# Video.net
KiCad netlist of a schematic drawn in Altium Designer
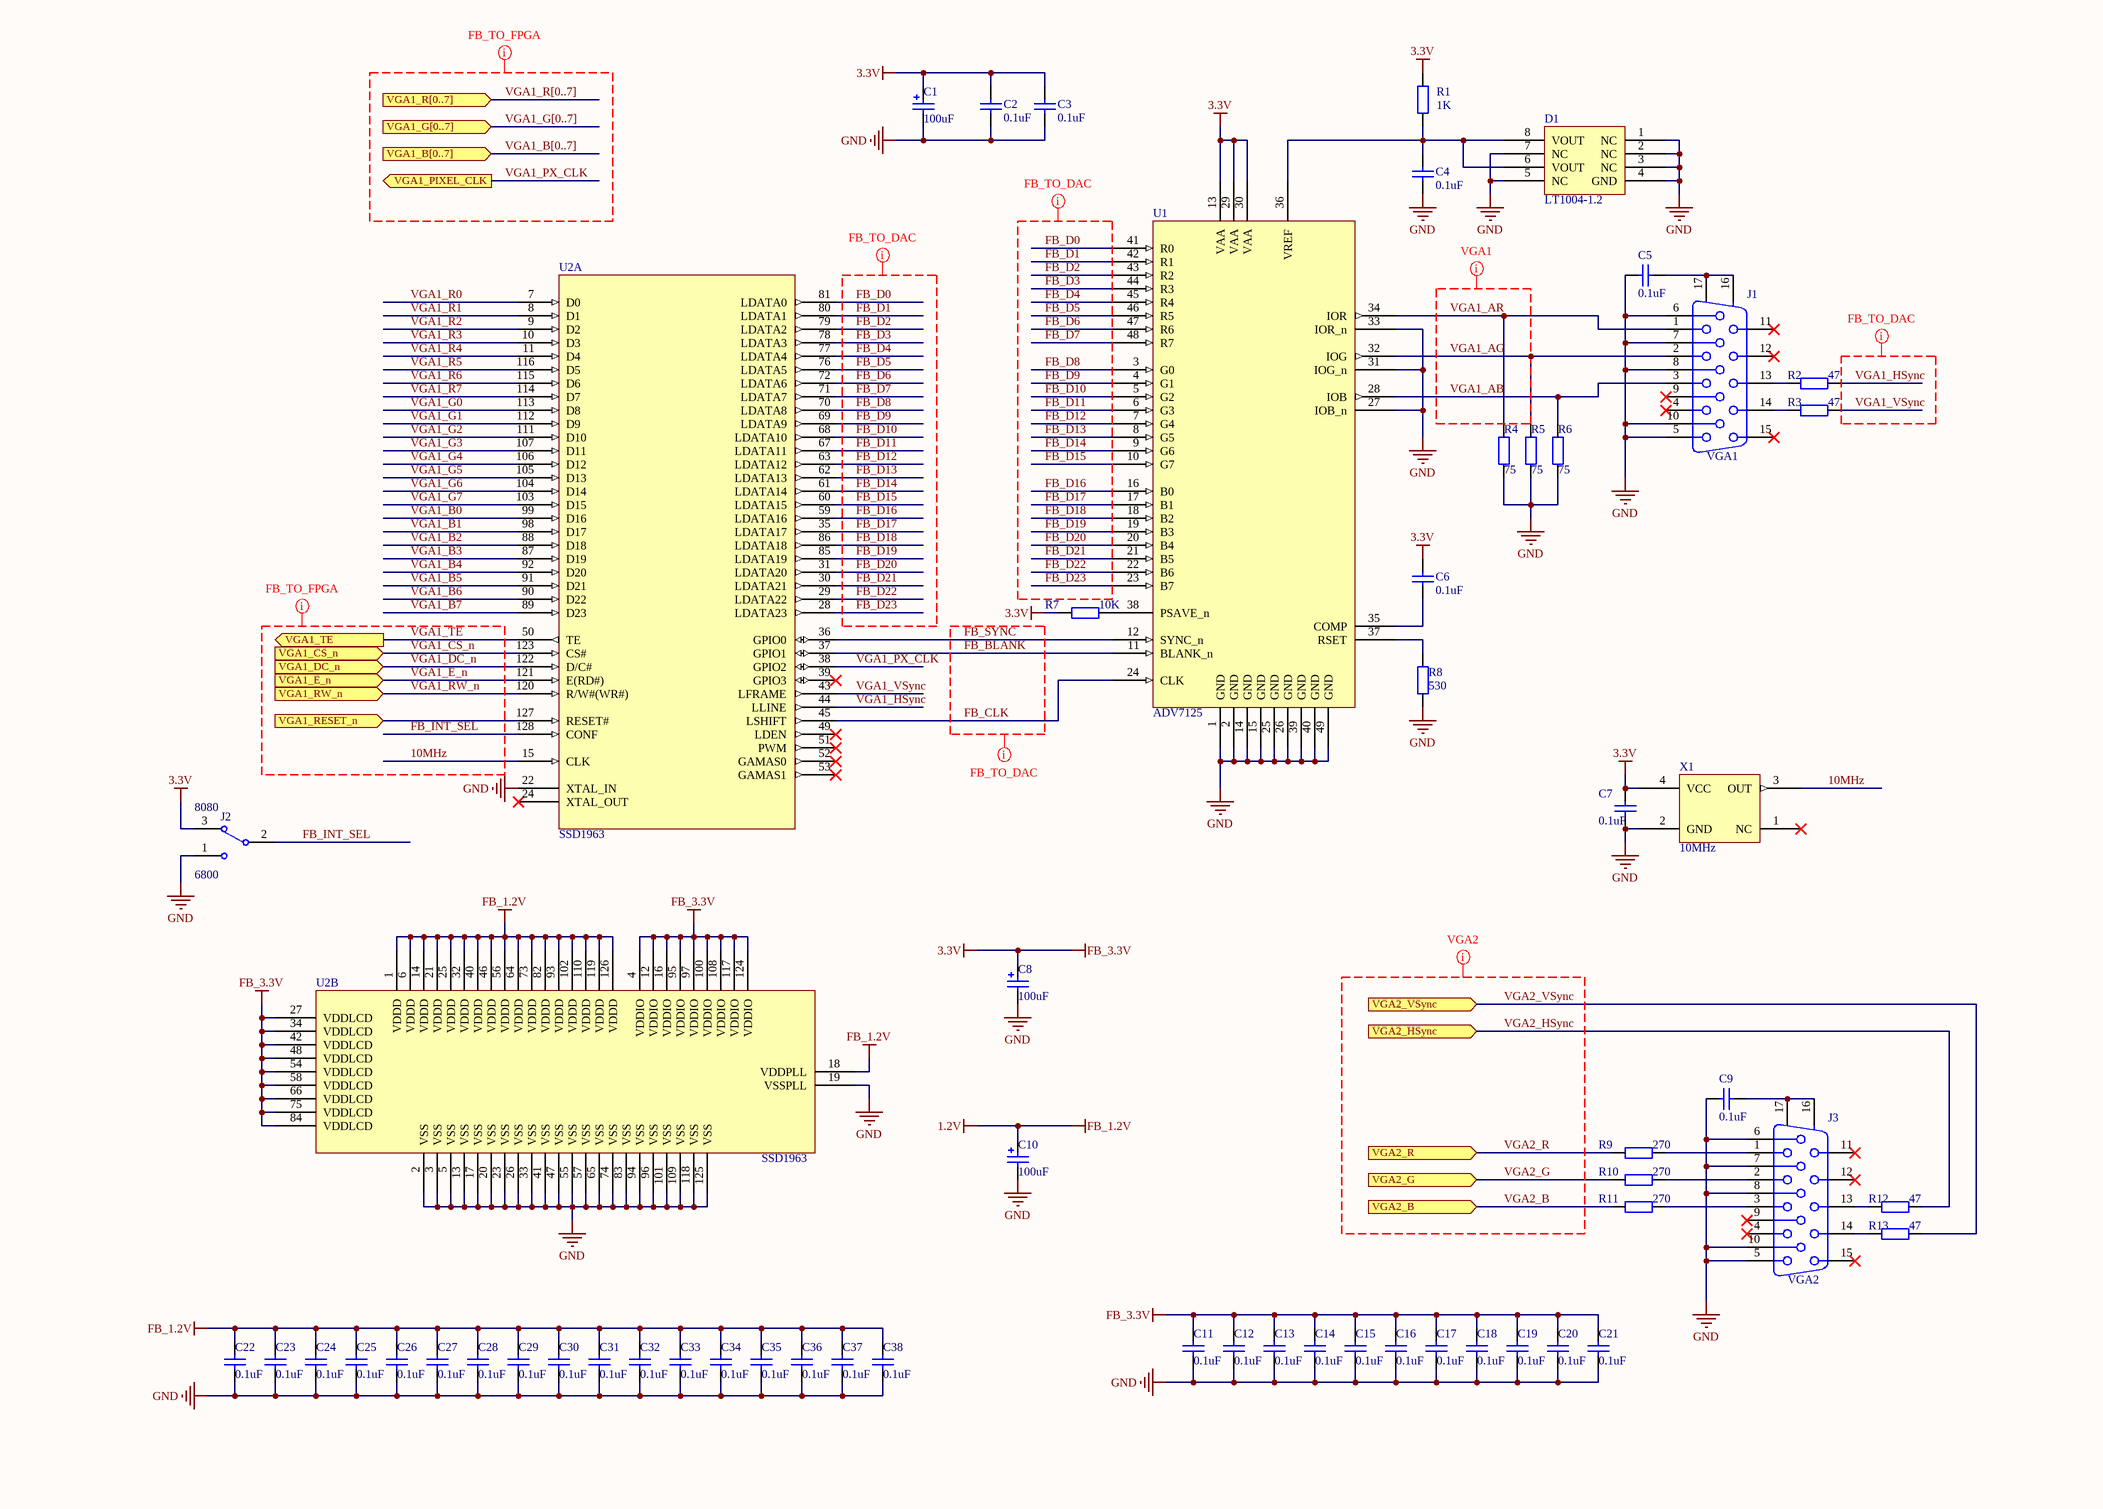
[diagram p0: Video.SchDoc]

(export (version "E")
  (design (tool "Eeschema 10.0.6"))
  (components
    (comp (ref "C1")
      (value "100uF")
      (footprint "C1206_POLARIZED")
      (description "Polarized Capacitor (Axial)")
      (fields (field (name "Comment") "Cap Pol2") (field (name "PUBLISHER") "Altium Limited"))
      (libsource (lib "Miscellaneous Devices") (part "Cap Pol2"))
    )
    (comp (ref "C2")
      (value "0.1uF")
      (footprint "0402")
      (description "Capacitor")
      (fields (field (name "Comment") "Cap") (field (name "PUBLISHER") "Altium Limited"))
      (libsource (lib "Miscellaneous Devices") (part "Cap"))
    )
    (comp (ref "C3")
      (value "0.1uF")
      (footprint "0402")
      (description "Capacitor")
      (fields (field (name "Comment") "Cap") (field (name "PUBLISHER") "Altium Limited"))
      (libsource (lib "Miscellaneous Devices") (part "Cap"))
    )
    (comp (ref "C4")
      (value "0.1uF")
      (footprint "0402")
      (description "Capacitor")
      (fields (field (name "Comment") "Cap") (field (name "PUBLISHER") "Altium Limited"))
      (libsource (lib "Miscellaneous Devices") (part "Cap"))
    )
    (comp (ref "C5")
      (value "0.1uF")
      (footprint "0402")
      (description "Capacitor")
      (fields (field (name "Comment") "Cap") (field (name "PUBLISHER") "Altium Limited"))
      (libsource (lib "Miscellaneous Devices") (part "Cap"))
    )
    (comp (ref "C6")
      (value "0.1uF")
      (footprint "0402")
      (description "Capacitor")
      (fields (field (name "Comment") "Cap") (field (name "PUBLISHER") "Altium Limited"))
      (libsource (lib "Miscellaneous Devices") (part "Cap"))
    )
    (comp (ref "C7")
      (value "0.1uF")
      (footprint "0402")
      (description "Capacitor")
      (fields (field (name "Comment") "Cap") (field (name "PUBLISHER") "Altium Limited"))
      (libsource (lib "Miscellaneous Devices") (part "Cap"))
    )
    (comp (ref "C8")
      (value "100uF")
      (footprint "C1206_POLARIZED")
      (description "Polarized Capacitor (Axial)")
      (fields (field (name "Comment") "Cap Pol2") (field (name "PUBLISHER") "Altium Limited"))
      (libsource (lib "Miscellaneous Devices") (part "Cap Pol2"))
    )
    (comp (ref "C9")
      (value "0.1uF")
      (footprint "0402")
      (description "Capacitor")
      (fields (field (name "Comment") "Cap") (field (name "PUBLISHER") "Altium Limited"))
      (libsource (lib "Miscellaneous Devices") (part "Cap"))
    )
    (comp (ref "C10")
      (value "100uF")
      (footprint "C1206_POLARIZED")
      (description "Polarized Capacitor (Axial)")
      (fields (field (name "Comment") "Cap Pol2") (field (name "PUBLISHER") "Altium Limited"))
      (libsource (lib "Miscellaneous Devices") (part "Cap Pol2"))
    )
    (comp (ref "C11")
      (value "0.1uF")
      (footprint "0402")
      (description "Capacitor")
      (fields (field (name "Comment") "Cap") (field (name "PUBLISHER") "Altium Limited"))
      (libsource (lib "Miscellaneous Devices") (part "Cap"))
    )
    (comp (ref "C12")
      (value "0.1uF")
      (footprint "0402")
      (description "Capacitor")
      (fields (field (name "Comment") "Cap") (field (name "PUBLISHER") "Altium Limited"))
      (libsource (lib "Miscellaneous Devices") (part "Cap"))
    )
    (comp (ref "C13")
      (value "0.1uF")
      (footprint "0402")
      (description "Capacitor")
      (fields (field (name "Comment") "Cap") (field (name "PUBLISHER") "Altium Limited"))
      (libsource (lib "Miscellaneous Devices") (part "Cap"))
    )
    (comp (ref "C14")
      (value "0.1uF")
      (footprint "0402")
      (description "Capacitor")
      (fields (field (name "Comment") "Cap") (field (name "PUBLISHER") "Altium Limited"))
      (libsource (lib "Miscellaneous Devices") (part "Cap"))
    )
    (comp (ref "C15")
      (value "0.1uF")
      (footprint "0402")
      (description "Capacitor")
      (fields (field (name "Comment") "Cap") (field (name "PUBLISHER") "Altium Limited"))
      (libsource (lib "Miscellaneous Devices") (part "Cap"))
    )
    (comp (ref "C16")
      (value "0.1uF")
      (footprint "0402")
      (description "Capacitor")
      (fields (field (name "Comment") "Cap") (field (name "PUBLISHER") "Altium Limited"))
      (libsource (lib "Miscellaneous Devices") (part "Cap"))
    )
    (comp (ref "C17")
      (value "0.1uF")
      (footprint "0402")
      (description "Capacitor")
      (fields (field (name "Comment") "Cap") (field (name "PUBLISHER") "Altium Limited"))
      (libsource (lib "Miscellaneous Devices") (part "Cap"))
    )
    (comp (ref "C18")
      (value "0.1uF")
      (footprint "0402")
      (description "Capacitor")
      (fields (field (name "Comment") "Cap") (field (name "PUBLISHER") "Altium Limited"))
      (libsource (lib "Miscellaneous Devices") (part "Cap"))
    )
    (comp (ref "C19")
      (value "0.1uF")
      (footprint "0402")
      (description "Capacitor")
      (fields (field (name "Comment") "Cap") (field (name "PUBLISHER") "Altium Limited"))
      (libsource (lib "Miscellaneous Devices") (part "Cap"))
    )
    (comp (ref "C20")
      (value "0.1uF")
      (footprint "0402")
      (description "Capacitor")
      (fields (field (name "Comment") "Cap") (field (name "PUBLISHER") "Altium Limited"))
      (libsource (lib "Miscellaneous Devices") (part "Cap"))
    )
    (comp (ref "C21")
      (value "0.1uF")
      (footprint "0402")
      (description "Capacitor")
      (fields (field (name "Comment") "Cap") (field (name "PUBLISHER") "Altium Limited"))
      (libsource (lib "Miscellaneous Devices") (part "Cap"))
    )
    (comp (ref "C22")
      (value "0.1uF")
      (footprint "0402")
      (description "Capacitor")
      (fields (field (name "Comment") "Cap") (field (name "PUBLISHER") "Altium Limited"))
      (libsource (lib "Miscellaneous Devices") (part "Cap"))
    )
    (comp (ref "C23")
      (value "0.1uF")
      (footprint "0402")
      (description "Capacitor")
      (fields (field (name "Comment") "Cap") (field (name "PUBLISHER") "Altium Limited"))
      (libsource (lib "Miscellaneous Devices") (part "Cap"))
    )
    (comp (ref "C24")
      (value "0.1uF")
      (footprint "0402")
      (description "Capacitor")
      (fields (field (name "Comment") "Cap") (field (name "PUBLISHER") "Altium Limited"))
      (libsource (lib "Miscellaneous Devices") (part "Cap"))
    )
    (comp (ref "C25")
      (value "0.1uF")
      (footprint "0402")
      (description "Capacitor")
      (fields (field (name "Comment") "Cap") (field (name "PUBLISHER") "Altium Limited"))
      (libsource (lib "Miscellaneous Devices") (part "Cap"))
    )
    (comp (ref "C26")
      (value "0.1uF")
      (footprint "0402")
      (description "Capacitor")
      (fields (field (name "Comment") "Cap") (field (name "PUBLISHER") "Altium Limited"))
      (libsource (lib "Miscellaneous Devices") (part "Cap"))
    )
    (comp (ref "C27")
      (value "0.1uF")
      (footprint "0402")
      (description "Capacitor")
      (fields (field (name "Comment") "Cap") (field (name "PUBLISHER") "Altium Limited"))
      (libsource (lib "Miscellaneous Devices") (part "Cap"))
    )
    (comp (ref "C28")
      (value "0.1uF")
      (footprint "0402")
      (description "Capacitor")
      (fields (field (name "Comment") "Cap") (field (name "PUBLISHER") "Altium Limited"))
      (libsource (lib "Miscellaneous Devices") (part "Cap"))
    )
    (comp (ref "C29")
      (value "0.1uF")
      (footprint "0402")
      (description "Capacitor")
      (fields (field (name "Comment") "Cap") (field (name "PUBLISHER") "Altium Limited"))
      (libsource (lib "Miscellaneous Devices") (part "Cap"))
    )
    (comp (ref "C30")
      (value "0.1uF")
      (footprint "0402")
      (description "Capacitor")
      (fields (field (name "Comment") "Cap") (field (name "PUBLISHER") "Altium Limited"))
      (libsource (lib "Miscellaneous Devices") (part "Cap"))
    )
    (comp (ref "C31")
      (value "0.1uF")
      (footprint "0402")
      (description "Capacitor")
      (fields (field (name "Comment") "Cap") (field (name "PUBLISHER") "Altium Limited"))
      (libsource (lib "Miscellaneous Devices") (part "Cap"))
    )
    (comp (ref "C32")
      (value "0.1uF")
      (footprint "0402")
      (description "Capacitor")
      (fields (field (name "Comment") "Cap") (field (name "PUBLISHER") "Altium Limited"))
      (libsource (lib "Miscellaneous Devices") (part "Cap"))
    )
    (comp (ref "C33")
      (value "0.1uF")
      (footprint "0402")
      (description "Capacitor")
      (fields (field (name "Comment") "Cap") (field (name "PUBLISHER") "Altium Limited"))
      (libsource (lib "Miscellaneous Devices") (part "Cap"))
    )
    (comp (ref "C34")
      (value "0.1uF")
      (footprint "0402")
      (description "Capacitor")
      (fields (field (name "Comment") "Cap") (field (name "PUBLISHER") "Altium Limited"))
      (libsource (lib "Miscellaneous Devices") (part "Cap"))
    )
    (comp (ref "C35")
      (value "0.1uF")
      (footprint "0402")
      (description "Capacitor")
      (fields (field (name "Comment") "Cap") (field (name "PUBLISHER") "Altium Limited"))
      (libsource (lib "Miscellaneous Devices") (part "Cap"))
    )
    (comp (ref "C36")
      (value "0.1uF")
      (footprint "0402")
      (description "Capacitor")
      (fields (field (name "Comment") "Cap") (field (name "PUBLISHER") "Altium Limited"))
      (libsource (lib "Miscellaneous Devices") (part "Cap"))
    )
    (comp (ref "C37")
      (value "0.1uF")
      (footprint "0402")
      (description "Capacitor")
      (fields (field (name "Comment") "Cap") (field (name "PUBLISHER") "Altium Limited"))
      (libsource (lib "Miscellaneous Devices") (part "Cap"))
    )
    (comp (ref "C38")
      (value "0.1uF")
      (footprint "0402")
      (description "Capacitor")
      (fields (field (name "Comment") "Cap") (field (name "PUBLISHER") "Altium Limited"))
      (libsource (lib "Miscellaneous Devices") (part "Cap"))
    )
    (comp (ref "D1") (value "LT1004-1.2") (footprint "S8") (libsource (lib "FPGA_board") (part "LT1004-1.2")))
    (comp (ref "J1")
      (value "VGA1")
      (footprint "FPGA_board:VGA_Socket")
      (description "Receptacle Assembly, 15-Pin, Sim Line Connector")
      (libsource (lib "Miscellaneous Connectors") (part "Connector 15"))
    )
    (comp (ref "J2")
      (value "FB_INTERFACE")
      (footprint "HDR1X3")
      (fields (field (name "PUBLISHER") "Altium Limited"))
      (libsource (lib "Miscellaneous Devices") (part "SW-SPDT"))
    )
    (comp (ref "J3")
      (value "VGA2")
      (footprint "FPGA_board:VGA_Socket")
      (description "Receptacle Assembly, 15-Pin, Sim Line Connector")
      (libsource (lib "Miscellaneous Connectors") (part "Connector 15"))
    )
    (comp (ref "R1")
      (value "1K")
      (footprint "J1-0603")
      (description "Resistor")
      (fields (field (name "Comment") "Res2") (field (name "PUBLISHER") "Altium Limited"))
      (libsource (lib "") (part "Res2_2"))
    )
    (comp (ref "R2")
      (value "47")
      (footprint "J1-0603")
      (description "Resistor")
      (fields (field (name "Comment") "Res2") (field (name "PUBLISHER") "Altium Limited"))
      (libsource (lib "") (part "Res2_1"))
    )
    (comp (ref "R3")
      (value "47")
      (footprint "J1-0603")
      (description "Resistor")
      (fields (field (name "Comment") "Res2") (field (name "PUBLISHER") "Altium Limited"))
      (libsource (lib "") (part "Res2_1"))
    )
    (comp (ref "R4")
      (value "75")
      (footprint "J1-0603")
      (description "Resistor")
      (fields (field (name "Comment") "Res2") (field (name "PUBLISHER") "Altium Limited"))
      (libsource (lib "") (part "Res2_2"))
    )
    (comp (ref "R5")
      (value "75")
      (footprint "J1-0603")
      (description "Resistor")
      (fields (field (name "Comment") "Res2") (field (name "PUBLISHER") "Altium Limited"))
      (libsource (lib "") (part "Res2_3"))
    )
    (comp (ref "R6")
      (value "75")
      (footprint "J1-0603")
      (description "Resistor")
      (fields (field (name "Comment") "Res2") (field (name "PUBLISHER") "Altium Limited"))
      (libsource (lib "") (part "Res2_3"))
    )
    (comp (ref "R7")
      (value "10K")
      (footprint "J1-0603")
      (description "Resistor")
      (fields (field (name "Comment") "Res2") (field (name "PUBLISHER") "Altium Limited"))
      (libsource (lib "") (part "Res2_1"))
    )
    (comp (ref "R8")
      (value "530")
      (footprint "J1-0603")
      (description "Resistor")
      (fields (field (name "Comment") "Res2") (field (name "PUBLISHER") "Altium Limited"))
      (libsource (lib "") (part "Res2_2"))
    )
    (comp (ref "R9")
      (value "270")
      (footprint "6-0805_N")
      (description "Resistor")
      (fields (field (name "Comment") "Res2") (field (name "PUBLISHER") "Altium Limited"))
      (libsource (lib "Miscellaneous Devices") (part "Res2"))
    )
    (comp (ref "R10")
      (value "270")
      (footprint "6-0805_N")
      (description "Resistor")
      (fields (field (name "Comment") "Res2") (field (name "PUBLISHER") "Altium Limited"))
      (libsource (lib "Miscellaneous Devices") (part "Res2"))
    )
    (comp (ref "R11")
      (value "270")
      (footprint "6-0805_N")
      (description "Resistor")
      (fields (field (name "Comment") "Res2") (field (name "PUBLISHER") "Altium Limited"))
      (libsource (lib "Miscellaneous Devices") (part "Res2"))
    )
    (comp (ref "R12")
      (value "47")
      (footprint "J1-0603")
      (description "Resistor")
      (fields (field (name "Comment") "Res2") (field (name "PUBLISHER") "Altium Limited"))
      (libsource (lib "") (part "Res2_1"))
    )
    (comp (ref "R13")
      (value "47")
      (footprint "J1-0603")
      (description "Resistor")
      (fields (field (name "Comment") "Res2") (field (name "PUBLISHER") "Altium Limited"))
      (libsource (lib "") (part "Res2_1"))
    )
    (comp (ref "U1")
      (value "ADV7125")
      (footprint "LFCSP_VQ48")
      (libsource (lib "FPGA_board") (part "ADV7125"))
    )
    (comp (ref "U2")
      (value "SSD1963")
      (footprint "LQFP128-0.4")
      (libsource (lib "FPGA_board") (part "SSD1963"))
    )
    (comp (ref "X1")
      (value "10MHz")
      (footprint "FOX924")
      (libsource (lib "FPGA_board") (part "FOX924B-10MHz"))
    )
  )
  (nets
    (net (code "1") (name "/10MHz") (class "Default")
      (node (ref "U2") (pin "15") (pinfunction "CLK_15") (pintype "input"))
      (node (ref "X1") (pin "3") (pinfunction "OUT_3") (pintype "output"))
    )
    (net (code "2") (name "/FB_BLANK") (class "Default")
      (node (ref "U1") (pin "11") (pinfunction "BLANK_n_11") (pintype "input"))
      (node (ref "U2") (pin "37") (pinfunction "GPIO1_37") (pintype "bidirectional"))
    )
    (net (code "3") (name "/FB_CLK") (class "Default")
      (node (ref "U1") (pin "24") (pinfunction "CLK_24") (pintype "input"))
      (node (ref "U2") (pin "45") (pinfunction "LSHIFT_45") (pintype "output"))
    )
    (net (code "4") (name "/FB_D0") (class "Default")
      (node (ref "U1") (pin "41") (pinfunction "R0_41") (pintype "input"))
      (node (ref "U2") (pin "81") (pinfunction "LDATA0_81") (pintype "output"))
    )
    (net (code "5") (name "/FB_D1") (class "Default")
      (node (ref "U1") (pin "42") (pinfunction "R1_42") (pintype "input"))
      (node (ref "U2") (pin "80") (pinfunction "LDATA1_80") (pintype "output"))
    )
    (net (code "6") (name "/FB_D2") (class "Default")
      (node (ref "U1") (pin "43") (pinfunction "R2_43") (pintype "input"))
      (node (ref "U2") (pin "79") (pinfunction "LDATA2_79") (pintype "output"))
    )
    (net (code "7") (name "/FB_D3") (class "Default")
      (node (ref "U1") (pin "44") (pinfunction "R3_44") (pintype "input"))
      (node (ref "U2") (pin "78") (pinfunction "LDATA3_78") (pintype "output"))
    )
    (net (code "8") (name "/FB_D4") (class "Default")
      (node (ref "U1") (pin "45") (pinfunction "R4_45") (pintype "input"))
      (node (ref "U2") (pin "77") (pinfunction "LDATA4_77") (pintype "output"))
    )
    (net (code "9") (name "/FB_D5") (class "Default")
      (node (ref "U1") (pin "46") (pinfunction "R5_46") (pintype "input"))
      (node (ref "U2") (pin "76") (pinfunction "LDATA5_76") (pintype "output"))
    )
    (net (code "10") (name "/FB_D6") (class "Default")
      (node (ref "U1") (pin "47") (pinfunction "R6_47") (pintype "input"))
      (node (ref "U2") (pin "72") (pinfunction "LDATA6_72") (pintype "output"))
    )
    (net (code "11") (name "/FB_D7") (class "Default")
      (node (ref "U1") (pin "48") (pinfunction "R7_48") (pintype "input"))
      (node (ref "U2") (pin "71") (pinfunction "LDATA7_71") (pintype "output"))
    )
    (net (code "12") (name "/FB_D8") (class "Default")
      (node (ref "U1") (pin "3") (pinfunction "G0_3") (pintype "input"))
      (node (ref "U2") (pin "70") (pinfunction "LDATA8_70") (pintype "output"))
    )
    (net (code "13") (name "/FB_D9") (class "Default")
      (node (ref "U1") (pin "4") (pinfunction "G1_4") (pintype "input"))
      (node (ref "U2") (pin "69") (pinfunction "LDATA9_69") (pintype "output"))
    )
    (net (code "14") (name "/FB_D10") (class "Default")
      (node (ref "U1") (pin "5") (pinfunction "G2_5") (pintype "input"))
      (node (ref "U2") (pin "68") (pinfunction "LDATA10_68") (pintype "output"))
    )
    (net (code "15") (name "/FB_D11") (class "Default")
      (node (ref "U1") (pin "6") (pinfunction "G3_6") (pintype "input"))
      (node (ref "U2") (pin "67") (pinfunction "LDATA11_67") (pintype "output"))
    )
    (net (code "16") (name "/FB_D12") (class "Default")
      (node (ref "U1") (pin "7") (pinfunction "G4_7") (pintype "input"))
      (node (ref "U2") (pin "63") (pinfunction "LDATA12_63") (pintype "output"))
    )
    (net (code "17") (name "/FB_D13") (class "Default")
      (node (ref "U1") (pin "8") (pinfunction "G5_8") (pintype "input"))
      (node (ref "U2") (pin "62") (pinfunction "LDATA13_62") (pintype "output"))
    )
    (net (code "18") (name "/FB_D14") (class "Default")
      (node (ref "U1") (pin "9") (pinfunction "G6_9") (pintype "input"))
      (node (ref "U2") (pin "61") (pinfunction "LDATA14_61") (pintype "output"))
    )
    (net (code "19") (name "/FB_D15") (class "Default")
      (node (ref "U1") (pin "10") (pinfunction "G7_10") (pintype "input"))
      (node (ref "U2") (pin "60") (pinfunction "LDATA15_60") (pintype "output"))
    )
    (net (code "20") (name "/FB_D16") (class "Default")
      (node (ref "U1") (pin "16") (pinfunction "B0_16") (pintype "input"))
      (node (ref "U2") (pin "59") (pinfunction "LDATA16_59") (pintype "output"))
    )
    (net (code "21") (name "/FB_D17") (class "Default")
      (node (ref "U1") (pin "17") (pinfunction "B1_17") (pintype "input"))
      (node (ref "U2") (pin "35") (pinfunction "LDATA17_35") (pintype "output"))
    )
    (net (code "22") (name "/FB_D18") (class "Default")
      (node (ref "U1") (pin "18") (pinfunction "B2_18") (pintype "input"))
      (node (ref "U2") (pin "86") (pinfunction "LDATA18_86") (pintype "output"))
    )
    (net (code "23") (name "/FB_D19") (class "Default")
      (node (ref "U1") (pin "19") (pinfunction "B3_19") (pintype "input"))
      (node (ref "U2") (pin "85") (pinfunction "LDATA19_85") (pintype "output"))
    )
    (net (code "24") (name "/FB_D20") (class "Default")
      (node (ref "U1") (pin "20") (pinfunction "B4_20") (pintype "input"))
      (node (ref "U2") (pin "31") (pinfunction "LDATA20_31") (pintype "output"))
    )
    (net (code "25") (name "/FB_D21") (class "Default")
      (node (ref "U1") (pin "21") (pinfunction "B5_21") (pintype "input"))
      (node (ref "U2") (pin "30") (pinfunction "LDATA21_30") (pintype "output"))
    )
    (net (code "26") (name "/FB_D22") (class "Default")
      (node (ref "U1") (pin "22") (pinfunction "B6_22") (pintype "input"))
      (node (ref "U2") (pin "29") (pinfunction "LDATA22_29") (pintype "output"))
    )
    (net (code "27") (name "/FB_D23") (class "Default")
      (node (ref "U1") (pin "23") (pinfunction "B7_23") (pintype "input"))
      (node (ref "U2") (pin "28") (pinfunction "LDATA23_28") (pintype "output"))
    )
    (net (code "28") (name "/FB_INT_SEL") (class "Default")
      (node (ref "J2") (pin "2") (pinfunction "2_2") (pintype "passive"))
      (node (ref "U2") (pin "128") (pinfunction "CONF_128") (pintype "input"))
    )
    (net (code "29") (name "/FB_SYNC") (class "Default")
      (node (ref "U1") (pin "12") (pinfunction "SYNC_n_12") (pintype "input"))
      (node (ref "U2") (pin "36") (pinfunction "GPIO0_36") (pintype "bidirectional"))
    )
    (net (code "30") (name "/VGA1_AB") (class "Default")
      (node (ref "J1") (pin "3") (pinfunction "3_3") (pintype "passive"))
      (node (ref "R6") (pin "1") (pinfunction "1_1") (pintype "passive"))
      (node (ref "U1") (pin "28") (pinfunction "IOB_28") (pintype "output"))
    )
    (net (code "31") (name "/VGA1_AG") (class "Default")
      (node (ref "J1") (pin "2") (pinfunction "2_2") (pintype "passive"))
      (node (ref "R5") (pin "1") (pinfunction "1_1") (pintype "passive"))
      (node (ref "U1") (pin "32") (pinfunction "IOG_32") (pintype "output"))
    )
    (net (code "32") (name "/VGA1_AR") (class "Default")
      (node (ref "J1") (pin "1") (pinfunction "1_1") (pintype "passive"))
      (node (ref "R4") (pin "2") (pinfunction "2_2") (pintype "passive"))
      (node (ref "U1") (pin "34") (pinfunction "IOR_34") (pintype "output"))
    )
    (net (code "33") (name "/VGA1_B0") (class "Default")
      (node (ref "U2") (pin "99") (pinfunction "D16_99") (pintype "input"))
    )
    (net (code "34") (name "/VGA1_B1") (class "Default")
      (node (ref "U2") (pin "98") (pinfunction "D17_98") (pintype "input"))
    )
    (net (code "35") (name "/VGA1_B2") (class "Default")
      (node (ref "U2") (pin "88") (pinfunction "D18_88") (pintype "input"))
    )
    (net (code "36") (name "/VGA1_B3") (class "Default")
      (node (ref "U2") (pin "87") (pinfunction "D19_87") (pintype "input"))
    )
    (net (code "37") (name "/VGA1_B4") (class "Default")
      (node (ref "U2") (pin "92") (pinfunction "D20_92") (pintype "input"))
    )
    (net (code "38") (name "/VGA1_B5") (class "Default")
      (node (ref "U2") (pin "91") (pinfunction "D21_91") (pintype "input"))
    )
    (net (code "39") (name "/VGA1_B6") (class "Default")
      (node (ref "U2") (pin "90") (pinfunction "D22_90") (pintype "input"))
    )
    (net (code "40") (name "/VGA1_B7") (class "Default")
      (node (ref "U2") (pin "89") (pinfunction "D23_89") (pintype "input"))
    )
    (net (code "42") (name "/VGA1_CS_n") (class "Default")
      (node (ref "U2") (pin "123") (pinfunction "CS#_123") (pintype "input"))
    )
    (net (code "43") (name "/VGA1_DC_n") (class "Default")
      (node (ref "U2") (pin "122") (pinfunction "D/C#_122") (pintype "input"))
    )
    (net (code "44") (name "/VGA1_E_n") (class "Default")
      (node (ref "U2") (pin "121") (pinfunction "E(RD#)_121") (pintype "input"))
    )
    (net (code "45") (name "/VGA1_G0") (class "Default")
      (node (ref "U2") (pin "113") (pinfunction "D8_113") (pintype "input"))
    )
    (net (code "46") (name "/VGA1_G1") (class "Default")
      (node (ref "U2") (pin "112") (pinfunction "D9_112") (pintype "input"))
    )
    (net (code "47") (name "/VGA1_G2") (class "Default")
      (node (ref "U2") (pin "111") (pinfunction "D10_111") (pintype "input"))
    )
    (net (code "48") (name "/VGA1_G3") (class "Default")
      (node (ref "U2") (pin "107") (pinfunction "D11_107") (pintype "input"))
    )
    (net (code "49") (name "/VGA1_G4") (class "Default")
      (node (ref "U2") (pin "106") (pinfunction "D12_106") (pintype "input"))
    )
    (net (code "50") (name "/VGA1_G5") (class "Default")
      (node (ref "U2") (pin "105") (pinfunction "D13_105") (pintype "input"))
    )
    (net (code "51") (name "/VGA1_G6") (class "Default")
      (node (ref "U2") (pin "104") (pinfunction "D14_104") (pintype "input"))
    )
    (net (code "52") (name "/VGA1_G7") (class "Default")
      (node (ref "U2") (pin "103") (pinfunction "D15_103") (pintype "input"))
    )
    (net (code "54") (name "/VGA1_HSync") (class "Default")
      (node (ref "R2") (pin "2") (pinfunction "2_2") (pintype "passive"))
      (node (ref "U2") (pin "44") (pinfunction "LLINE_44") (pintype "output"))
    )
    (net (code "55") (name "/VGA1_PX_CLK") (class "Default")
      (node (ref "U2") (pin "38") (pinfunction "GPIO2_38") (pintype "bidirectional"))
    )
    (net (code "56") (name "/VGA1_R0") (class "Default")
      (node (ref "U2") (pin "7") (pinfunction "D0_7") (pintype "input"))
    )
    (net (code "57") (name "/VGA1_R1") (class "Default")
      (node (ref "U2") (pin "8") (pinfunction "D1_8") (pintype "input"))
    )
    (net (code "58") (name "/VGA1_R2") (class "Default")
      (node (ref "U2") (pin "9") (pinfunction "D2_9") (pintype "input"))
    )
    (net (code "59") (name "/VGA1_R3") (class "Default")
      (node (ref "U2") (pin "10") (pinfunction "D3_10") (pintype "input"))
    )
    (net (code "60") (name "/VGA1_R4") (class "Default")
      (node (ref "U2") (pin "11") (pinfunction "D4_11") (pintype "input"))
    )
    (net (code "61") (name "/VGA1_R5") (class "Default")
      (node (ref "U2") (pin "116") (pinfunction "D5_116") (pintype "input"))
    )
    (net (code "62") (name "/VGA1_R6") (class "Default")
      (node (ref "U2") (pin "115") (pinfunction "D6_115") (pintype "input"))
    )
    (net (code "63") (name "/VGA1_R7") (class "Default")
      (node (ref "U2") (pin "114") (pinfunction "D7_114") (pintype "input"))
    )
    (net (code "64") (name "/VGA1_RESET_n") (class "Default")
      (node (ref "U2") (pin "127") (pinfunction "RESET#_127") (pintype "input"))
    )
    (net (code "65") (name "/VGA1_RW_n") (class "Default")
      (node (ref "U2") (pin "120") (pinfunction "R/W#(WR#)_120") (pintype "input"))
    )
    (net (code "67") (name "/VGA1_TE") (class "Default")
      (node (ref "U2") (pin "50") (pinfunction "TE_50") (pintype "output"))
    )
    (net (code "68") (name "/VGA1_VSync") (class "Default")
      (node (ref "R3") (pin "2") (pinfunction "2_2") (pintype "passive"))
      (node (ref "U2") (pin "43") (pinfunction "LFRAME_43") (pintype "output"))
    )
    (net (code "69") (name "/VGA2_B") (class "Default")
      (node (ref "R11") (pin "2") (pinfunction "2_2") (pintype "passive"))
    )
    (net (code "70") (name "/VGA2_G") (class "Default")
      (node (ref "R10") (pin "2") (pinfunction "2_2") (pintype "passive"))
    )
    (net (code "71") (name "/VGA2_HSync") (class "Default")
      (node (ref "R12") (pin "2") (pinfunction "2_2") (pintype "passive"))
    )
    (net (code "72") (name "/VGA2_R") (class "Default")
      (node (ref "R9") (pin "2") (pinfunction "2_2") (pintype "passive"))
    )
    (net (code "73") (name "/VGA2_VSync") (class "Default")
      (node (ref "R13") (pin "2") (pinfunction "2_2") (pintype "passive"))
    )
    (net (code "74") (name "1.2V") (class "Default")
      (node (ref "C10") (pin "1") (pinfunction "1_1") (pintype "passive"))
      (node (ref "C22") (pin "1") (pinfunction "1_1") (pintype "passive"))
      (node (ref "C23") (pin "1") (pinfunction "1_1") (pintype "passive"))
      (node (ref "C24") (pin "1") (pinfunction "1_1") (pintype "passive"))
      (node (ref "C25") (pin "1") (pinfunction "1_1") (pintype "passive"))
      (node (ref "C26") (pin "1") (pinfunction "1_1") (pintype "passive"))
      (node (ref "C27") (pin "1") (pinfunction "1_1") (pintype "passive"))
      (node (ref "C28") (pin "1") (pinfunction "1_1") (pintype "passive"))
      (node (ref "C29") (pin "1") (pinfunction "1_1") (pintype "passive"))
      (node (ref "C30") (pin "1") (pinfunction "1_1") (pintype "passive"))
      (node (ref "C31") (pin "1") (pinfunction "1_1") (pintype "passive"))
      (node (ref "C32") (pin "1") (pinfunction "1_1") (pintype "passive"))
      (node (ref "C33") (pin "1") (pinfunction "1_1") (pintype "passive"))
      (node (ref "C34") (pin "1") (pinfunction "1_1") (pintype "passive"))
      (node (ref "C35") (pin "1") (pinfunction "1_1") (pintype "passive"))
      (node (ref "C36") (pin "1") (pinfunction "1_1") (pintype "passive"))
      (node (ref "C37") (pin "1") (pinfunction "1_1") (pintype "passive"))
      (node (ref "C38") (pin "1") (pinfunction "1_1") (pintype "passive"))
      (node (ref "U2") (pin "1") (pinfunction "VDDD_1") (pintype "power_in"))
      (node (ref "U2") (pin "102") (pinfunction "VDDD_102") (pintype "power_in"))
      (node (ref "U2") (pin "110") (pinfunction "VDDD_110") (pintype "power_in"))
      (node (ref "U2") (pin "119") (pinfunction "VDDD_119") (pintype "power_in"))
      (node (ref "U2") (pin "126") (pinfunction "VDDD_126") (pintype "power_in"))
      (node (ref "U2") (pin "14") (pinfunction "VDDD_14") (pintype "power_in"))
      (node (ref "U2") (pin "18") (pinfunction "VDDPLL_18") (pintype "power_in"))
      (node (ref "U2") (pin "21") (pinfunction "VDDD_21") (pintype "power_in"))
      (node (ref "U2") (pin "25") (pinfunction "VDDD_25") (pintype "power_in"))
      (node (ref "U2") (pin "32") (pinfunction "VDDD_32") (pintype "power_in"))
      (node (ref "U2") (pin "40") (pinfunction "VDDD_40") (pintype "power_in"))
      (node (ref "U2") (pin "46") (pinfunction "VDDD_46") (pintype "power_in"))
      (node (ref "U2") (pin "56") (pinfunction "VDDD_56") (pintype "power_in"))
      (node (ref "U2") (pin "6") (pinfunction "VDDD_6") (pintype "power_in"))
      (node (ref "U2") (pin "64") (pinfunction "VDDD_64") (pintype "power_in"))
      (node (ref "U2") (pin "73") (pinfunction "VDDD_73") (pintype "power_in"))
      (node (ref "U2") (pin "82") (pinfunction "VDDD_82") (pintype "power_in"))
      (node (ref "U2") (pin "93") (pinfunction "VDDD_93") (pintype "power_in"))
    )
    (net (code "75") (name "3.3V") (class "Default")
      (node (ref "C1") (pin "1") (pinfunction "1_1") (pintype "passive"))
      (node (ref "C11") (pin "1") (pinfunction "1_1") (pintype "passive"))
      (node (ref "C12") (pin "1") (pinfunction "1_1") (pintype "passive"))
      (node (ref "C13") (pin "1") (pinfunction "1_1") (pintype "passive"))
      (node (ref "C14") (pin "1") (pinfunction "1_1") (pintype "passive"))
      (node (ref "C15") (pin "1") (pinfunction "1_1") (pintype "passive"))
      (node (ref "C16") (pin "1") (pinfunction "1_1") (pintype "passive"))
      (node (ref "C17") (pin "1") (pinfunction "1_1") (pintype "passive"))
      (node (ref "C18") (pin "1") (pinfunction "1_1") (pintype "passive"))
      (node (ref "C19") (pin "1") (pinfunction "1_1") (pintype "passive"))
      (node (ref "C2") (pin "2") (pinfunction "2_2") (pintype "passive"))
      (node (ref "C20") (pin "1") (pinfunction "1_1") (pintype "passive"))
      (node (ref "C21") (pin "1") (pinfunction "1_1") (pintype "passive"))
      (node (ref "C3") (pin "2") (pinfunction "2_2") (pintype "passive"))
      (node (ref "C6") (pin "2") (pinfunction "2_2") (pintype "passive"))
      (node (ref "C7") (pin "1") (pinfunction "1_1") (pintype "passive"))
      (node (ref "C8") (pin "1") (pinfunction "1_1") (pintype "passive"))
      (node (ref "J2") (pin "3") (pinfunction "3_3") (pintype "passive"))
      (node (ref "R1") (pin "2") (pinfunction "2_2") (pintype "passive"))
      (node (ref "R7") (pin "1") (pinfunction "1_1") (pintype "passive"))
      (node (ref "U1") (pin "13") (pinfunction "VAA_13") (pintype "power_in"))
      (node (ref "U1") (pin "29") (pinfunction "VAA_29") (pintype "power_in"))
      (node (ref "U1") (pin "30") (pinfunction "VAA_30") (pintype "power_in"))
      (node (ref "U2") (pin "100") (pinfunction "VDDIO_100") (pintype "power_in"))
      (node (ref "U2") (pin "108") (pinfunction "VDDIO_108") (pintype "power_in"))
      (node (ref "U2") (pin "117") (pinfunction "VDDIO_117") (pintype "power_in"))
      (node (ref "U2") (pin "12") (pinfunction "VDDIO_12") (pintype "power_in"))
      (node (ref "U2") (pin "124") (pinfunction "VDDIO_124") (pintype "power_in"))
      (node (ref "U2") (pin "16") (pinfunction "VDDIO_16") (pintype "power_in"))
      (node (ref "U2") (pin "27") (pinfunction "VDDLCD_27") (pintype "power_in"))
      (node (ref "U2") (pin "34") (pinfunction "VDDLCD_34") (pintype "power_in"))
      (node (ref "U2") (pin "4") (pinfunction "VDDIO_4") (pintype "power_in"))
      (node (ref "U2") (pin "42") (pinfunction "VDDLCD_42") (pintype "power_in"))
      (node (ref "U2") (pin "48") (pinfunction "VDDLCD_48") (pintype "power_in"))
      (node (ref "U2") (pin "54") (pinfunction "VDDLCD_54") (pintype "power_in"))
      (node (ref "U2") (pin "58") (pinfunction "VDDLCD_58") (pintype "power_in"))
      (node (ref "U2") (pin "66") (pinfunction "VDDLCD_66") (pintype "power_in"))
      (node (ref "U2") (pin "75") (pinfunction "VDDLCD_75") (pintype "power_in"))
      (node (ref "U2") (pin "84") (pinfunction "VDDLCD_84") (pintype "power_in"))
      (node (ref "U2") (pin "95") (pinfunction "VDDIO_95") (pintype "power_in"))
      (node (ref "U2") (pin "97") (pinfunction "VDDIO_97") (pintype "power_in"))
      (node (ref "X1") (pin "4") (pinfunction "VCC_4") (pintype "power_in"))
    )
    (net (code "76") (name "GND") (class "Default")
      (node (ref "C1") (pin "2") (pinfunction "2_2") (pintype "passive"))
      (node (ref "C10") (pin "2") (pinfunction "2_2") (pintype "passive"))
      (node (ref "C11") (pin "2") (pinfunction "2_2") (pintype "passive"))
      (node (ref "C12") (pin "2") (pinfunction "2_2") (pintype "passive"))
      (node (ref "C13") (pin "2") (pinfunction "2_2") (pintype "passive"))
      (node (ref "C14") (pin "2") (pinfunction "2_2") (pintype "passive"))
      (node (ref "C15") (pin "2") (pinfunction "2_2") (pintype "passive"))
      (node (ref "C16") (pin "2") (pinfunction "2_2") (pintype "passive"))
      (node (ref "C17") (pin "2") (pinfunction "2_2") (pintype "passive"))
      (node (ref "C18") (pin "2") (pinfunction "2_2") (pintype "passive"))
      (node (ref "C19") (pin "2") (pinfunction "2_2") (pintype "passive"))
      (node (ref "C2") (pin "1") (pinfunction "1_1") (pintype "passive"))
      (node (ref "C20") (pin "2") (pinfunction "2_2") (pintype "passive"))
      (node (ref "C21") (pin "2") (pinfunction "2_2") (pintype "passive"))
      (node (ref "C22") (pin "2") (pinfunction "2_2") (pintype "passive"))
      (node (ref "C23") (pin "2") (pinfunction "2_2") (pintype "passive"))
      (node (ref "C24") (pin "2") (pinfunction "2_2") (pintype "passive"))
      (node (ref "C25") (pin "2") (pinfunction "2_2") (pintype "passive"))
      (node (ref "C26") (pin "2") (pinfunction "2_2") (pintype "passive"))
      (node (ref "C27") (pin "2") (pinfunction "2_2") (pintype "passive"))
      (node (ref "C28") (pin "2") (pinfunction "2_2") (pintype "passive"))
      (node (ref "C29") (pin "2") (pinfunction "2_2") (pintype "passive"))
      (node (ref "C3") (pin "1") (pinfunction "1_1") (pintype "passive"))
      (node (ref "C30") (pin "2") (pinfunction "2_2") (pintype "passive"))
      (node (ref "C31") (pin "2") (pinfunction "2_2") (pintype "passive"))
      (node (ref "C32") (pin "2") (pinfunction "2_2") (pintype "passive"))
      (node (ref "C33") (pin "2") (pinfunction "2_2") (pintype "passive"))
      (node (ref "C34") (pin "2") (pinfunction "2_2") (pintype "passive"))
      (node (ref "C35") (pin "2") (pinfunction "2_2") (pintype "passive"))
      (node (ref "C36") (pin "2") (pinfunction "2_2") (pintype "passive"))
      (node (ref "C37") (pin "2") (pinfunction "2_2") (pintype "passive"))
      (node (ref "C38") (pin "2") (pinfunction "2_2") (pintype "passive"))
      (node (ref "C4") (pin "2") (pinfunction "2_2") (pintype "passive"))
      (node (ref "C5") (pin "1") (pinfunction "1_1") (pintype "passive"))
      (node (ref "C7") (pin "2") (pinfunction "2_2") (pintype "passive"))
      (node (ref "C8") (pin "2") (pinfunction "2_2") (pintype "passive"))
      (node (ref "C9") (pin "1") (pinfunction "1_1") (pintype "passive"))
      (node (ref "D1") (pin "1") (pinfunction "NC_1") (pintype "passive"))
      (node (ref "D1") (pin "2") (pinfunction "NC_2") (pintype "passive"))
      (node (ref "D1") (pin "3") (pinfunction "NC_3") (pintype "passive"))
      (node (ref "D1") (pin "4") (pinfunction "GND_4") (pintype "passive"))
      (node (ref "D1") (pin "5") (pinfunction "NC_5") (pintype "passive"))
      (node (ref "D1") (pin "7") (pinfunction "NC_7") (pintype "passive"))
      (node (ref "J1") (pin "10") (pinfunction "10_10") (pintype "passive"))
      (node (ref "J1") (pin "5") (pinfunction "5_5") (pintype "passive"))
      (node (ref "J1") (pin "6") (pinfunction "6_6") (pintype "passive"))
      (node (ref "J1") (pin "7") (pinfunction "7_7") (pintype "passive"))
      (node (ref "J1") (pin "8") (pinfunction "8_8") (pintype "passive"))
      (node (ref "J2") (pin "1") (pinfunction "1_1") (pintype "passive"))
      (node (ref "J3") (pin "10") (pinfunction "10_10") (pintype "passive"))
      (node (ref "J3") (pin "5") (pinfunction "5_5") (pintype "passive"))
      (node (ref "J3") (pin "6") (pinfunction "6_6") (pintype "passive"))
      (node (ref "J3") (pin "7") (pinfunction "7_7") (pintype "passive"))
      (node (ref "J3") (pin "8") (pinfunction "8_8") (pintype "passive"))
      (node (ref "R4") (pin "1") (pinfunction "1_1") (pintype "passive"))
      (node (ref "R5") (pin "2") (pinfunction "2_2") (pintype "passive"))
      (node (ref "R6") (pin "2") (pinfunction "2_2") (pintype "passive"))
      (node (ref "R8") (pin "1") (pinfunction "1_1") (pintype "passive"))
      (node (ref "U1") (pin "1") (pinfunction "GND_1") (pintype "power_in"))
      (node (ref "U1") (pin "14") (pinfunction "GND_14") (pintype "power_in"))
      (node (ref "U1") (pin "15") (pinfunction "GND_15") (pintype "power_in"))
      (node (ref "U1") (pin "2") (pinfunction "GND_2") (pintype "power_in"))
      (node (ref "U1") (pin "25") (pinfunction "GND_25") (pintype "power_in"))
      (node (ref "U1") (pin "26") (pinfunction "GND_26") (pintype "power_in"))
      (node (ref "U1") (pin "27") (pinfunction "IOB_n_27") (pintype "passive"))
      (node (ref "U1") (pin "31") (pinfunction "IOG_n_31") (pintype "passive"))
      (node (ref "U1") (pin "33") (pinfunction "IOR_n_33") (pintype "passive"))
      (node (ref "U1") (pin "39") (pinfunction "GND_39") (pintype "power_in"))
      (node (ref "U1") (pin "40") (pinfunction "GND_40") (pintype "power_in"))
      (node (ref "U1") (pin "49") (pinfunction "GND_49") (pintype "power_in"))
      (node (ref "U2") (pin "101") (pinfunction "VSS_101") (pintype "power_in"))
      (node (ref "U2") (pin "109") (pinfunction "VSS_109") (pintype "power_in"))
      (node (ref "U2") (pin "118") (pinfunction "VSS_118") (pintype "power_in"))
      (node (ref "U2") (pin "125") (pinfunction "VSS_125") (pintype "power_in"))
      (node (ref "U2") (pin "13") (pinfunction "VSS_13") (pintype "power_in"))
      (node (ref "U2") (pin "17") (pinfunction "VSS_17") (pintype "power_in"))
      (node (ref "U2") (pin "19") (pinfunction "VSSPLL_19") (pintype "power_in"))
      (node (ref "U2") (pin "2") (pinfunction "VSS_2") (pintype "power_in"))
      (node (ref "U2") (pin "20") (pinfunction "VSS_20") (pintype "power_in"))
      (node (ref "U2") (pin "22") (pinfunction "XTAL_IN_22") (pintype "passive"))
      (node (ref "U2") (pin "23") (pinfunction "VSS_23") (pintype "power_in"))
      (node (ref "U2") (pin "26") (pinfunction "VSS_26") (pintype "power_in"))
      (node (ref "U2") (pin "3") (pinfunction "VSS_3") (pintype "power_in"))
      (node (ref "U2") (pin "33") (pinfunction "VSS_33") (pintype "power_in"))
      (node (ref "U2") (pin "41") (pinfunction "VSS_41") (pintype "power_in"))
      (node (ref "U2") (pin "47") (pinfunction "VSS_47") (pintype "power_in"))
      (node (ref "U2") (pin "5") (pinfunction "VSS_5") (pintype "power_in"))
      (node (ref "U2") (pin "55") (pinfunction "VSS_55") (pintype "power_in"))
      (node (ref "U2") (pin "57") (pinfunction "VSS_57") (pintype "power_in"))
      (node (ref "U2") (pin "65") (pinfunction "VSS_65") (pintype "power_in"))
      (node (ref "U2") (pin "74") (pinfunction "VSS_74") (pintype "power_in"))
      (node (ref "U2") (pin "83") (pinfunction "VSS_83") (pintype "power_in"))
      (node (ref "U2") (pin "94") (pinfunction "VSS_94") (pintype "power_in"))
      (node (ref "U2") (pin "96") (pinfunction "VSS_96") (pintype "power_in"))
      (node (ref "X1") (pin "2") (pinfunction "GND_2") (pintype "power_in"))
    )
    (net (code "77") (name "Net-(J1-MH1)") (class "Default")
      (node (ref "C5") (pin "2") (pinfunction "2_2") (pintype "passive"))
      (node (ref "J1") (pin "16") (pinfunction "MH1_16") (pintype "passive"))
      (node (ref "J1") (pin "17") (pinfunction "MH2_17") (pintype "passive"))
    )
    (net (code "78") (name "Net-(J1-Pad13)") (class "Default")
      (node (ref "J1") (pin "13") (pinfunction "13_13") (pintype "passive"))
      (node (ref "R2") (pin "1") (pinfunction "1_1") (pintype "passive"))
    )
    (net (code "79") (name "Net-(J1-Pad14)") (class "Default")
      (node (ref "J1") (pin "14") (pinfunction "14_14") (pintype "passive"))
      (node (ref "R3") (pin "1") (pinfunction "1_1") (pintype "passive"))
    )
    (net (code "80") (name "Net-(J3-MH1)") (class "Default")
      (node (ref "C9") (pin "2") (pinfunction "2_2") (pintype "passive"))
      (node (ref "J3") (pin "16") (pinfunction "MH1_16") (pintype "passive"))
      (node (ref "J3") (pin "17") (pinfunction "MH2_17") (pintype "passive"))
    )
    (net (code "81") (name "Net-(J3-Pad1)") (class "Default")
      (node (ref "J3") (pin "1") (pinfunction "1_1") (pintype "passive"))
      (node (ref "R9") (pin "1") (pinfunction "1_1") (pintype "passive"))
    )
    (net (code "82") (name "Net-(J3-Pad2)") (class "Default")
      (node (ref "J3") (pin "2") (pinfunction "2_2") (pintype "passive"))
      (node (ref "R10") (pin "1") (pinfunction "1_1") (pintype "passive"))
    )
    (net (code "83") (name "Net-(J3-Pad3)") (class "Default")
      (node (ref "J3") (pin "3") (pinfunction "3_3") (pintype "passive"))
      (node (ref "R11") (pin "1") (pinfunction "1_1") (pintype "passive"))
    )
    (net (code "84") (name "Net-(J3-Pad13)") (class "Default")
      (node (ref "J3") (pin "13") (pinfunction "13_13") (pintype "passive"))
      (node (ref "R12") (pin "1") (pinfunction "1_1") (pintype "passive"))
    )
    (net (code "85") (name "Net-(J3-Pad14)") (class "Default")
      (node (ref "J3") (pin "14") (pinfunction "14_14") (pintype "passive"))
      (node (ref "R13") (pin "1") (pinfunction "1_1") (pintype "passive"))
    )
    (net (code "86") (name "Net-(U1-COMP)") (class "Default")
      (node (ref "C6") (pin "1") (pinfunction "1_1") (pintype "passive"))
      (node (ref "U1") (pin "35") (pinfunction "COMP_35") (pintype "passive"))
    )
    (net (code "87") (name "Net-(U1-PSAVE_n)") (class "Default")
      (node (ref "R7") (pin "2") (pinfunction "2_2") (pintype "passive"))
      (node (ref "U1") (pin "38") (pinfunction "PSAVE_n_38") (pintype "passive"))
    )
    (net (code "88") (name "Net-(U1-RSET)") (class "Default")
      (node (ref "R8") (pin "2") (pinfunction "2_2") (pintype "passive"))
      (node (ref "U1") (pin "37") (pinfunction "RSET_37") (pintype "passive"))
    )
    (net (code "89") (name "Net-(U1-VREF)") (class "Default")
      (node (ref "C4") (pin "1") (pinfunction "1_1") (pintype "passive"))
      (node (ref "D1") (pin "6") (pinfunction "VOUT_6") (pintype "passive"))
      (node (ref "D1") (pin "8") (pinfunction "VOUT_8") (pintype "passive"))
      (node (ref "R1") (pin "1") (pinfunction "1_1") (pintype "passive"))
      (node (ref "U1") (pin "36") (pinfunction "VREF_36") (pintype "power_in"))
    )
    (net (code "90") (name "unconnected-(J1-Pad4)") (class "Default")
      (node (ref "J1") (pin "4") (pinfunction "4_4") (pintype "passive+no_connect"))
    )
    (net (code "91") (name "unconnected-(J1-Pad9)") (class "Default")
      (node (ref "J1") (pin "9") (pinfunction "9_9") (pintype "passive+no_connect"))
    )
    (net (code "92") (name "unconnected-(J1-Pad11)") (class "Default")
      (node (ref "J1") (pin "11") (pinfunction "11_11") (pintype "passive+no_connect"))
    )
    (net (code "93") (name "unconnected-(J1-Pad12)") (class "Default")
      (node (ref "J1") (pin "12") (pinfunction "12_12") (pintype "passive+no_connect"))
    )
    (net (code "94") (name "unconnected-(J1-Pad15)") (class "Default")
      (node (ref "J1") (pin "15") (pinfunction "15_15") (pintype "passive+no_connect"))
    )
    (net (code "95") (name "unconnected-(J3-Pad4)") (class "Default")
      (node (ref "J3") (pin "4") (pinfunction "4_4") (pintype "passive+no_connect"))
    )
    (net (code "96") (name "unconnected-(J3-Pad9)") (class "Default")
      (node (ref "J3") (pin "9") (pinfunction "9_9") (pintype "passive+no_connect"))
    )
    (net (code "97") (name "unconnected-(J3-Pad11)") (class "Default")
      (node (ref "J3") (pin "11") (pinfunction "11_11") (pintype "passive+no_connect"))
    )
    (net (code "98") (name "unconnected-(J3-Pad12)") (class "Default")
      (node (ref "J3") (pin "12") (pinfunction "12_12") (pintype "passive+no_connect"))
    )
    (net (code "99") (name "unconnected-(J3-Pad15)") (class "Default")
      (node (ref "J3") (pin "15") (pinfunction "15_15") (pintype "passive+no_connect"))
    )
    (net (code "100") (name "unconnected-(U2A-GAMAS0-Pad52)") (class "Default")
      (node (ref "U2") (pin "52") (pinfunction "GAMAS0_52") (pintype "output+no_connect"))
    )
    (net (code "101") (name "unconnected-(U2A-GAMAS1-Pad53)") (class "Default")
      (node (ref "U2") (pin "53") (pinfunction "GAMAS1_53") (pintype "output+no_connect"))
    )
    (net (code "102") (name "unconnected-(U2A-GPIO3-Pad39)") (class "Default")
      (node (ref "U2") (pin "39") (pinfunction "GPIO3_39") (pintype "bidirectional+no_connect"))
    )
    (net (code "103") (name "unconnected-(U2A-LDEN-Pad49)") (class "Default")
      (node (ref "U2") (pin "49") (pinfunction "LDEN_49") (pintype "output+no_connect"))
    )
    (net (code "104") (name "unconnected-(U2A-PWM-Pad51)") (class "Default")
      (node (ref "U2") (pin "51") (pinfunction "PWM_51") (pintype "output+no_connect"))
    )
    (net (code "105") (name "unconnected-(U2A-XTAL_OUT-Pad24)") (class "Default")
      (node (ref "U2") (pin "24") (pinfunction "XTAL_OUT_24") (pintype "passive+no_connect"))
    )
    (net (code "106") (name "unconnected-(X1-NC-Pad1)") (class "Default")
      (node (ref "X1") (pin "1") (pinfunction "NC_1") (pintype "passive+no_connect"))
    )
  )
)
